# schematic_v_2.net
KiCad netlist of a schematic drawn in EAGLE
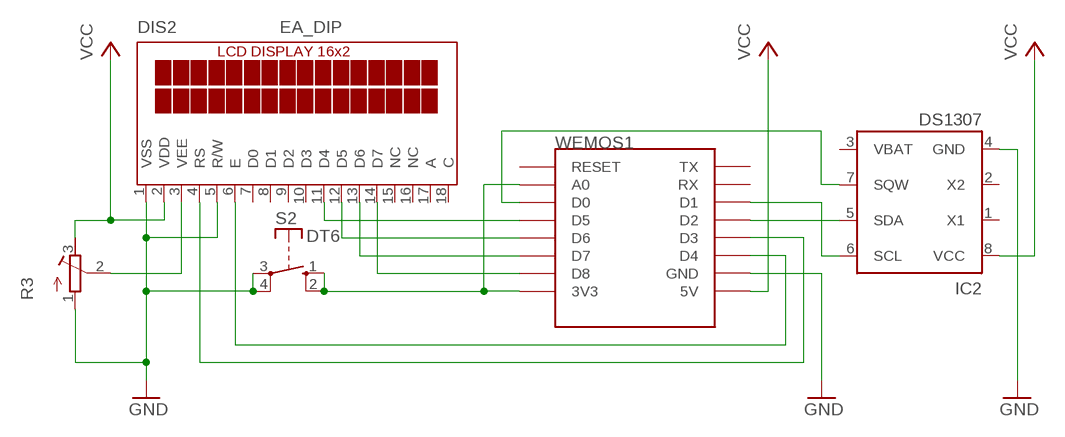
[diagram p0: schematic, sheet 1]

(export (version "E")
  (design (tool "Eeschema 10.0.6"))
  (components
    (comp (ref "DIS2")
      (value "EA_DIP")
      (footprint "eagle-import:EA_DIP")
      (libsource (lib "eagle-import") (part "EA_DIP"))
    )
    (comp (ref "IC2")
      (value "DS1307")
      (footprint "eagle-import:DIL08")
      (libsource (lib "eagle-import") (part "DS1307"))
    )
    (comp (ref "R3")
      (value "R-TRIMMTS63Y")
      (footprint "eagle-import:RTRIMTS63Y")
      (libsource (lib "eagle-import") (part "R-TRIMMTS63Y"))
    )
    (comp (ref "S2")
      (value "DT6")
      (footprint "eagle-import:DT6")
      (libsource (lib "eagle-import") (part "DT6"))
    )
    (comp (ref "WEMOS1")
      (value "WEMOS-D1-MINI")
      (footprint "eagle-import:WEMOS-D1-MINI")
      (libsource (lib "eagle-import") (part "WEMOS-D1-MINI"))
    )
  )
  (nets
    (net (code "1") (name "GND") (class "Default")
      (node (ref "DIS2") (pin "1") (pinfunction "VSS_1") (pintype "power_in"))
      (node (ref "DIS2") (pin "5") (pinfunction "R/W_5") (pintype "input"))
      (node (ref "IC2") (pin "4") (pinfunction "GND_4") (pintype "power_in"))
      (node (ref "R3") (pin "1") (pinfunction "A_1") (pintype "passive"))
      (node (ref "S2") (pin "3") (pinfunction "P_3") (pintype "passive"))
      (node (ref "S2") (pin "4") (pinfunction "P_4") (pintype "passive"))
      (node (ref "WEMOS1") (pin "GND") (pinfunction "GND_GND") (pintype "bidirectional"))
    )
    (net (code "2") (name "Net-(DIS2-D4)") (class "Default")
      (node (ref "DIS2") (pin "11") (pinfunction "D4_11") (pintype "input"))
      (node (ref "WEMOS1") (pin "D5") (pinfunction "D5_D5") (pintype "bidirectional"))
    )
    (net (code "3") (name "Net-(DIS2-D5)") (class "Default")
      (node (ref "DIS2") (pin "12") (pinfunction "D5_12") (pintype "input"))
      (node (ref "WEMOS1") (pin "D6") (pinfunction "D6_D6") (pintype "bidirectional"))
    )
    (net (code "4") (name "Net-(DIS2-D6)") (class "Default")
      (node (ref "DIS2") (pin "13") (pinfunction "D6_13") (pintype "input"))
      (node (ref "WEMOS1") (pin "D7") (pinfunction "D7_D7") (pintype "bidirectional"))
    )
    (net (code "5") (name "Net-(DIS2-D7)") (class "Default")
      (node (ref "DIS2") (pin "14") (pinfunction "D7_14") (pintype "input"))
      (node (ref "WEMOS1") (pin "D8") (pinfunction "D8_D8") (pintype "bidirectional"))
    )
    (net (code "6") (name "Net-(DIS2-E)") (class "Default")
      (node (ref "DIS2") (pin "6") (pinfunction "E_6") (pintype "input"))
      (node (ref "WEMOS1") (pin "D4") (pinfunction "D4_D4") (pintype "bidirectional"))
    )
    (net (code "7") (name "Net-(DIS2-RS)") (class "Default")
      (node (ref "DIS2") (pin "4") (pinfunction "RS_4") (pintype "input"))
      (node (ref "WEMOS1") (pin "D3") (pinfunction "D3_D3") (pintype "bidirectional"))
    )
    (net (code "8") (name "Net-(DIS2-VEE)") (class "Default")
      (node (ref "DIS2") (pin "3") (pinfunction "VEE_3") (pintype "power_in"))
      (node (ref "R3") (pin "2") (pinfunction "S_2") (pintype "passive"))
    )
    (net (code "9") (name "Net-(IC2-SCL)") (class "Default")
      (node (ref "IC2") (pin "6") (pinfunction "SCL_6") (pintype "input"))
      (node (ref "WEMOS1") (pin "D1") (pinfunction "D1_D1") (pintype "bidirectional"))
    )
    (net (code "10") (name "Net-(IC2-SDA)") (class "Default")
      (node (ref "IC2") (pin "5") (pinfunction "SDA_5") (pintype "bidirectional"))
      (node (ref "WEMOS1") (pin "D2") (pinfunction "D2_D2") (pintype "bidirectional"))
    )
    (net (code "11") (name "Net-(IC2-SQW)") (class "Default")
      (node (ref "IC2") (pin "7") (pinfunction "SQW_7") (pintype "open_collector"))
      (node (ref "WEMOS1") (pin "D0") (pinfunction "D0_D0") (pintype "bidirectional"))
    )
    (net (code "12") (name "Net-(S2-S-Pad1)") (class "Default")
      (node (ref "S2") (pin "1") (pinfunction "S_1") (pintype "passive"))
      (node (ref "S2") (pin "2") (pinfunction "S_2") (pintype "passive"))
      (node (ref "WEMOS1") (pin "3V3") (pinfunction "3V3_3V3") (pintype "bidirectional"))
      (node (ref "WEMOS1") (pin "A0") (pinfunction "A0_A0") (pintype "bidirectional"))
    )
    (net (code "13") (name "VCC") (class "Default")
      (node (ref "DIS2") (pin "2") (pinfunction "VDD_2") (pintype "power_in"))
      (node (ref "IC2") (pin "8") (pinfunction "VCC_8") (pintype "power_in"))
      (node (ref "R3") (pin "3") (pinfunction "E_3") (pintype "passive"))
      (node (ref "WEMOS1") (pin "5V") (pinfunction "5V_5V") (pintype "bidirectional"))
    )
    (net (code "14") (name "unconnected-(DIS2-A-Pad17)") (class "Default")
      (node (ref "DIS2") (pin "17") (pinfunction "A_17") (pintype "passive"))
    )
    (net (code "15") (name "unconnected-(DIS2-C-Pad18)") (class "Default")
      (node (ref "DIS2") (pin "18") (pinfunction "C_18") (pintype "passive"))
    )
    (net (code "16") (name "unconnected-(DIS2-D0-Pad7)") (class "Default")
      (node (ref "DIS2") (pin "7") (pinfunction "D0_7") (pintype "input"))
    )
    (net (code "17") (name "unconnected-(DIS2-D1-Pad8)") (class "Default")
      (node (ref "DIS2") (pin "8") (pinfunction "D1_8") (pintype "input"))
    )
    (net (code "18") (name "unconnected-(DIS2-D2-Pad9)") (class "Default")
      (node (ref "DIS2") (pin "9") (pinfunction "D2_9") (pintype "input"))
    )
    (net (code "19") (name "unconnected-(DIS2-D3-Pad10)") (class "Default")
      (node (ref "DIS2") (pin "10") (pinfunction "D3_10") (pintype "input"))
    )
    (net (code "20") (name "unconnected-(DIS2-NC-Pad15)") (class "Default")
      (node (ref "DIS2") (pin "15") (pinfunction "NC_15") (pintype "no_connect"))
    )
    (net (code "21") (name "unconnected-(DIS2-NC-Pad16)") (class "Default")
      (node (ref "DIS2") (pin "16") (pinfunction "NC_16") (pintype "no_connect"))
    )
    (net (code "22") (name "unconnected-(IC2-VBAT-Pad3)") (class "Default")
      (node (ref "IC2") (pin "3") (pinfunction "VBAT_3") (pintype "passive"))
    )
    (net (code "23") (name "unconnected-(IC2-X1-Pad1)") (class "Default")
      (node (ref "IC2") (pin "1") (pinfunction "X1_1") (pintype "input"))
    )
    (net (code "24") (name "unconnected-(IC2-X2-Pad2)") (class "Default")
      (node (ref "IC2") (pin "2") (pinfunction "X2_2") (pintype "output"))
    )
    (net (code "25") (name "unconnected-(WEMOS1-PadRESET)") (class "Default")
      (node (ref "WEMOS1") (pin "RESET") (pinfunction "RESET_RESET") (pintype "bidirectional"))
    )
    (net (code "26") (name "unconnected-(WEMOS1-PadRX)") (class "Default")
      (node (ref "WEMOS1") (pin "RX") (pinfunction "RX_RX") (pintype "bidirectional"))
    )
    (net (code "27") (name "unconnected-(WEMOS1-PadTX)") (class "Default")
      (node (ref "WEMOS1") (pin "TX") (pinfunction "TX_TX") (pintype "bidirectional"))
    )
  )
)
